# IO.net
KiCad netlist of a schematic drawn in Altium Designer
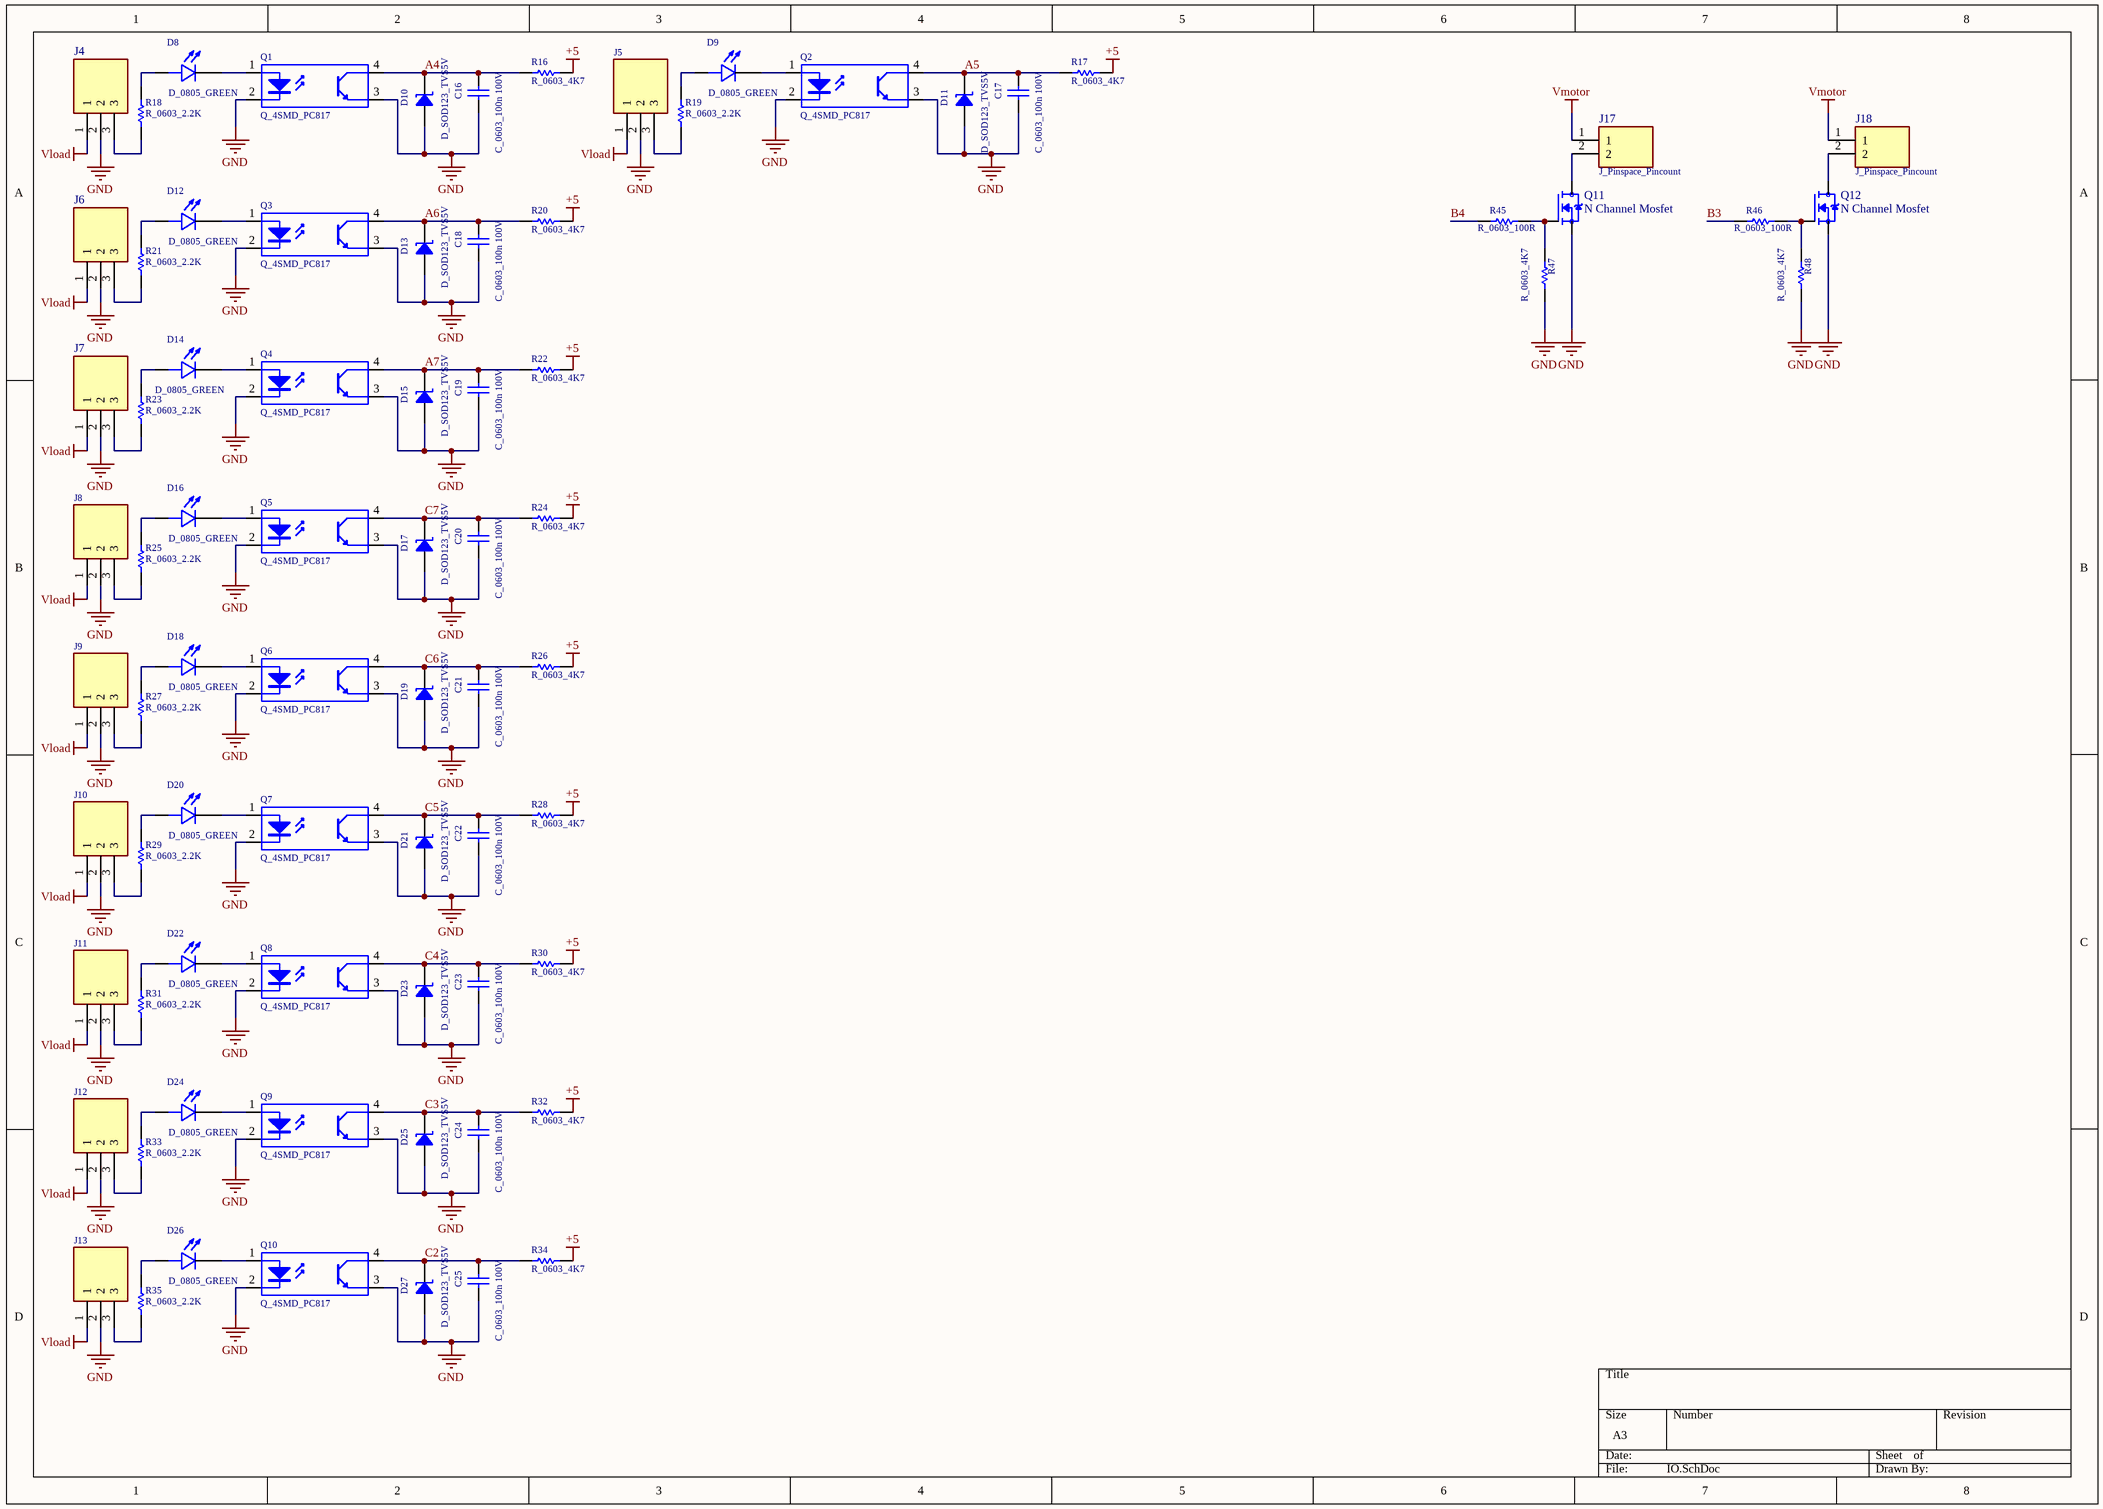
[diagram p0: IO.SchDoc]

(export (version "E")
  (design (tool "Eeschema 10.0.6"))
  (components
    (comp (ref "C16")
      (value "C_0603_100n 100V")
      (footprint "CAP 1206")
      (description "Capacitor")
      (fields (field (name "PUBLISHER") "Altium Limited"))
      (libsource (lib "HUE") (part "Cap"))
    )
    (comp (ref "C17")
      (value "C_0603_100n 100V")
      (footprint "CAP 1206")
      (description "Capacitor")
      (fields (field (name "PUBLISHER") "Altium Limited"))
      (libsource (lib "HUE") (part "Cap"))
    )
    (comp (ref "C18")
      (value "C_0603_100n 100V")
      (footprint "CAP 1206")
      (description "Capacitor")
      (fields (field (name "PUBLISHER") "Altium Limited"))
      (libsource (lib "HUE") (part "Cap"))
    )
    (comp (ref "C19")
      (value "C_0603_100n 100V")
      (footprint "CAP 1206")
      (description "Capacitor")
      (fields (field (name "PUBLISHER") "Altium Limited"))
      (libsource (lib "HUE") (part "Cap"))
    )
    (comp (ref "C20")
      (value "C_0603_100n 100V")
      (footprint "CAP 1206")
      (description "Capacitor")
      (fields (field (name "PUBLISHER") "Altium Limited"))
      (libsource (lib "HUE") (part "Cap"))
    )
    (comp (ref "C21")
      (value "C_0603_100n 100V")
      (footprint "CAP 1206")
      (description "Capacitor")
      (fields (field (name "PUBLISHER") "Altium Limited"))
      (libsource (lib "HUE") (part "Cap"))
    )
    (comp (ref "C22")
      (value "C_0603_100n 100V")
      (footprint "CAP 1206")
      (description "Capacitor")
      (fields (field (name "PUBLISHER") "Altium Limited"))
      (libsource (lib "HUE") (part "Cap"))
    )
    (comp (ref "C23")
      (value "C_0603_100n 100V")
      (footprint "CAP 1206")
      (description "Capacitor")
      (fields (field (name "PUBLISHER") "Altium Limited"))
      (libsource (lib "HUE") (part "Cap"))
    )
    (comp (ref "C24")
      (value "C_0603_100n 100V")
      (footprint "CAP 1206")
      (description "Capacitor")
      (fields (field (name "PUBLISHER") "Altium Limited"))
      (libsource (lib "HUE") (part "Cap"))
    )
    (comp (ref "C25")
      (value "C_0603_100n 100V")
      (footprint "CAP 1206")
      (description "Capacitor")
      (fields (field (name "PUBLISHER") "Altium Limited"))
      (libsource (lib "HUE") (part "Cap"))
    )
    (comp (ref "D8")
      (value "D_0805_GREEN")
      (footprint "Led 0603")
      (description "Led")
      (fields (field (name "MP") "SML-D12FWT86") (field (name "MF") "Rohm"))
      (libsource (lib "HUE") (part "Led"))
    )
    (comp (ref "D9")
      (value "D_0805_GREEN")
      (footprint "Led 0603")
      (description "Led")
      (fields (field (name "MP") "SML-D12FWT86") (field (name "MF") "Rohm"))
      (libsource (lib "HUE") (part "Led"))
    )
    (comp (ref "D10")
      (value "D_SOD123_TVS5V")
      (footprint "SOD-123")
      (description "Rectifier Diode")
      (libsource (lib "HUE") (part "DIODE TVS UNI"))
    )
    (comp (ref "D11")
      (value "D_SOD123_TVS5V")
      (footprint "SOD-123")
      (description "Rectifier Diode")
      (libsource (lib "HUE") (part "DIODE TVS UNI"))
    )
    (comp (ref "D12")
      (value "D_0805_GREEN")
      (footprint "Led 0603")
      (description "Led")
      (fields (field (name "MP") "SML-D12FWT86") (field (name "MF") "Rohm"))
      (libsource (lib "HUE") (part "Led"))
    )
    (comp (ref "D13")
      (value "D_SOD123_TVS5V")
      (footprint "SOD-123")
      (description "Rectifier Diode")
      (libsource (lib "HUE") (part "DIODE TVS UNI"))
    )
    (comp (ref "D14")
      (value "D_0805_GREEN")
      (footprint "Led 0603")
      (description "Led")
      (fields (field (name "MP") "SML-D12FWT86") (field (name "MF") "Rohm"))
      (libsource (lib "HUE") (part "Led"))
    )
    (comp (ref "D15")
      (value "D_SOD123_TVS5V")
      (footprint "SOD-123")
      (description "Rectifier Diode")
      (libsource (lib "HUE") (part "DIODE TVS UNI"))
    )
    (comp (ref "D16")
      (value "D_0805_GREEN")
      (footprint "Led 0603")
      (description "Led")
      (fields (field (name "MP") "SML-D12FWT86") (field (name "MF") "Rohm"))
      (libsource (lib "HUE") (part "Led"))
    )
    (comp (ref "D17")
      (value "D_SOD123_TVS5V")
      (footprint "SOD-123")
      (description "Rectifier Diode")
      (libsource (lib "HUE") (part "DIODE TVS UNI"))
    )
    (comp (ref "D18")
      (value "D_0805_GREEN")
      (footprint "Led 0603")
      (description "Led")
      (fields (field (name "MP") "SML-D12FWT86") (field (name "MF") "Rohm"))
      (libsource (lib "HUE") (part "Led"))
    )
    (comp (ref "D19")
      (value "D_SOD123_TVS5V")
      (footprint "SOD-123")
      (description "Rectifier Diode")
      (libsource (lib "HUE") (part "DIODE TVS UNI"))
    )
    (comp (ref "D20")
      (value "D_0805_GREEN")
      (footprint "Led 0603")
      (description "Led")
      (fields (field (name "MP") "SML-D12FWT86") (field (name "MF") "Rohm"))
      (libsource (lib "HUE") (part "Led"))
    )
    (comp (ref "D21")
      (value "D_SOD123_TVS5V")
      (footprint "SOD-123")
      (description "Rectifier Diode")
      (libsource (lib "HUE") (part "DIODE TVS UNI"))
    )
    (comp (ref "D22")
      (value "D_0805_GREEN")
      (footprint "Led 0603")
      (description "Led")
      (fields (field (name "MP") "SML-D12FWT86") (field (name "MF") "Rohm"))
      (libsource (lib "HUE") (part "Led"))
    )
    (comp (ref "D23")
      (value "D_SOD123_TVS5V")
      (footprint "SOD-123")
      (description "Rectifier Diode")
      (libsource (lib "HUE") (part "DIODE TVS UNI"))
    )
    (comp (ref "D24")
      (value "D_0805_GREEN")
      (footprint "Led 0603")
      (description "Led")
      (fields (field (name "MP") "SML-D12FWT86") (field (name "MF") "Rohm"))
      (libsource (lib "HUE") (part "Led"))
    )
    (comp (ref "D25")
      (value "D_SOD123_TVS5V")
      (footprint "SOD-123")
      (description "Rectifier Diode")
      (libsource (lib "HUE") (part "DIODE TVS UNI"))
    )
    (comp (ref "D26")
      (value "D_0805_GREEN")
      (footprint "Led 0603")
      (description "Led")
      (fields (field (name "MP") "SML-D12FWT86") (field (name "MF") "Rohm"))
      (libsource (lib "HUE") (part "Led"))
    )
    (comp (ref "D27")
      (value "D_SOD123_TVS5V")
      (footprint "SOD-123")
      (description "Rectifier Diode")
      (libsource (lib "HUE") (part "DIODE TVS UNI"))
    )
    (comp (ref "J4")
      (value "J_Pinspace_Pincount")
      (footprint "3 Pin PCB STB 5.08")
      (fields (field (name "MF") "{'manufacturer': u'CUI'}") (field (name "MP") "TBP02R1-381-03BE"))
      (libsource (lib "HUE") (part "3 Pin PCB Terminal Block"))
    )
    (comp (ref "J5")
      (value "J_Pinspace_Pincount")
      (footprint "3 Pin PCB STB 5.08")
      (fields (field (name "MF") "{'manufacturer': u'CUI'}") (field (name "MP") "TBP02R1-381-03BE"))
      (libsource (lib "HUE") (part "3 Pin PCB Terminal Block"))
    )
    (comp (ref "J6")
      (value "J_Pinspace_Pincount")
      (footprint "3 Pin PCB STB 5.08")
      (fields (field (name "MF") "{'manufacturer': u'CUI'}") (field (name "MP") "TBP02R1-381-03BE"))
      (libsource (lib "HUE") (part "3 Pin PCB Terminal Block"))
    )
    (comp (ref "J7")
      (value "J_Pinspace_Pincount")
      (footprint "3 Pin PCB STB 5.08")
      (fields (field (name "MF") "{'manufacturer': u'CUI'}") (field (name "MP") "TBP02R1-381-03BE"))
      (libsource (lib "HUE") (part "3 Pin PCB Terminal Block"))
    )
    (comp (ref "J8")
      (value "J_Pinspace_Pincount")
      (footprint "3 Pin PCB STB 5.08")
      (fields (field (name "MF") "{'manufacturer': u'CUI'}") (field (name "MP") "TBP02R1-381-03BE"))
      (libsource (lib "HUE") (part "3 Pin PCB Terminal Block"))
    )
    (comp (ref "J9")
      (value "J_Pinspace_Pincount")
      (footprint "3 Pin PCB STB 5.08")
      (fields (field (name "MF") "{'manufacturer': u'CUI'}") (field (name "MP") "TBP02R1-381-03BE"))
      (libsource (lib "HUE") (part "3 Pin PCB Terminal Block"))
    )
    (comp (ref "J10")
      (value "J_Pinspace_Pincount")
      (footprint "3 Pin PCB STB 5.08")
      (fields (field (name "MF") "{'manufacturer': u'CUI'}") (field (name "MP") "TBP02R1-381-03BE"))
      (libsource (lib "HUE") (part "3 Pin PCB Terminal Block"))
    )
    (comp (ref "J11")
      (value "J_Pinspace_Pincount")
      (footprint "3 Pin PCB STB 5.08")
      (fields (field (name "MF") "{'manufacturer': u'CUI'}") (field (name "MP") "TBP02R1-381-03BE"))
      (libsource (lib "HUE") (part "3 Pin PCB Terminal Block"))
    )
    (comp (ref "J12")
      (value "J_Pinspace_Pincount")
      (footprint "3 Pin PCB STB 5.08")
      (fields (field (name "MF") "{'manufacturer': u'CUI'}") (field (name "MP") "TBP02R1-381-03BE"))
      (libsource (lib "HUE") (part "3 Pin PCB Terminal Block"))
    )
    (comp (ref "J13")
      (value "J_Pinspace_Pincount")
      (footprint "3 Pin PCB STB 5.08")
      (fields (field (name "MF") "{'manufacturer': u'CUI'}") (field (name "MP") "TBP02R1-381-03BE"))
      (libsource (lib "HUE") (part "3 Pin PCB Terminal Block"))
    )
    (comp (ref "J17")
      (value "J_Pinspace_Pincount")
      (footprint "2 Pin PCB STB 5.08")
      (fields (field (name "MF") "CUI Devices") (field (name "MP") "TBP02R1-381-02BE"))
      (libsource (lib "HUE") (part "2 Pin PCB Terminal Block"))
    )
    (comp (ref "J18")
      (value "J_Pinspace_Pincount")
      (footprint "2 Pin PCB STB 5.08")
      (fields (field (name "MF") "CUI Devices") (field (name "MP") "TBP02R1-381-02BE"))
      (libsource (lib "HUE") (part "2 Pin PCB Terminal Block"))
    )
    (comp (ref "Q1")
      (value "Q_4SMD_PC817")
      (footprint "4-SMD")
      (description "Opto-Coupler")
      (libsource (lib "HUE") (part "Opto Coupler"))
    )
    (comp (ref "Q2")
      (value "Q_4SMD_PC817")
      (footprint "4-SMD")
      (description "Opto-Coupler")
      (libsource (lib "HUE") (part "Opto Coupler"))
    )
    (comp (ref "Q3")
      (value "Q_4SMD_PC817")
      (footprint "4-SMD")
      (description "Opto-Coupler")
      (libsource (lib "HUE") (part "Opto Coupler"))
    )
    (comp (ref "Q4")
      (value "Q_4SMD_PC817")
      (footprint "4-SMD")
      (description "Opto-Coupler")
      (libsource (lib "HUE") (part "Opto Coupler"))
    )
    (comp (ref "Q5")
      (value "Q_4SMD_PC817")
      (footprint "4-SMD")
      (description "Opto-Coupler")
      (libsource (lib "HUE") (part "Opto Coupler"))
    )
    (comp (ref "Q6")
      (value "Q_4SMD_PC817")
      (footprint "4-SMD")
      (description "Opto-Coupler")
      (libsource (lib "HUE") (part "Opto Coupler"))
    )
    (comp (ref "Q7")
      (value "Q_4SMD_PC817")
      (footprint "4-SMD")
      (description "Opto-Coupler")
      (libsource (lib "HUE") (part "Opto Coupler"))
    )
    (comp (ref "Q8")
      (value "Q_4SMD_PC817")
      (footprint "4-SMD")
      (description "Opto-Coupler")
      (libsource (lib "HUE") (part "Opto Coupler"))
    )
    (comp (ref "Q9")
      (value "Q_4SMD_PC817")
      (footprint "4-SMD")
      (description "Opto-Coupler")
      (libsource (lib "HUE") (part "Opto Coupler"))
    )
    (comp (ref "Q10")
      (value "Q_4SMD_PC817")
      (footprint "4-SMD")
      (description "Opto-Coupler")
      (libsource (lib "HUE") (part "Opto Coupler"))
    )
    (comp (ref "Q11")
      (value "N Channel Mosfet")
      (footprint "TO-252")
      (fields (field (name "MP") "IRLR2705PBF") (field (name "MF") "Infineon Technologies"))
      (libsource (lib "HUE") (part "N Channel Mosfet"))
    )
    (comp (ref "Q12")
      (value "N Channel Mosfet")
      (footprint "TO-252")
      (fields (field (name "MP") "IRLR2705PBF") (field (name "MF") "Infineon Technologies"))
      (libsource (lib "HUE") (part "N Channel Mosfet"))
    )
    (comp (ref "R16")
      (value "R_0603_4K7")
      (footprint "RES 1206")
      (description "Resistor")
      (fields (field (name "PUBLISHER") "Altium Limited"))
      (libsource (lib "HUE") (part "Res"))
    )
    (comp (ref "R17")
      (value "R_0603_4K7")
      (footprint "RES 1206")
      (description "Resistor")
      (fields (field (name "PUBLISHER") "Altium Limited"))
      (libsource (lib "HUE") (part "Res"))
    )
    (comp (ref "R18")
      (value "R_0603_2.2K")
      (footprint "RES 1206")
      (description "Resistor")
      (fields (field (name "PUBLISHER") "Altium Limited"))
      (libsource (lib "HUE") (part "Res"))
    )
    (comp (ref "R19")
      (value "R_0603_2.2K")
      (footprint "RES 1206")
      (description "Resistor")
      (fields (field (name "PUBLISHER") "Altium Limited"))
      (libsource (lib "HUE") (part "Res"))
    )
    (comp (ref "R20")
      (value "R_0603_4K7")
      (footprint "RES 1206")
      (description "Resistor")
      (fields (field (name "PUBLISHER") "Altium Limited"))
      (libsource (lib "HUE") (part "Res"))
    )
    (comp (ref "R21")
      (value "R_0603_2.2K")
      (footprint "RES 1206")
      (description "Resistor")
      (fields (field (name "PUBLISHER") "Altium Limited"))
      (libsource (lib "HUE") (part "Res"))
    )
    (comp (ref "R22")
      (value "R_0603_4K7")
      (footprint "RES 1206")
      (description "Resistor")
      (fields (field (name "PUBLISHER") "Altium Limited"))
      (libsource (lib "HUE") (part "Res"))
    )
    (comp (ref "R23")
      (value "R_0603_2.2K")
      (footprint "RES 1206")
      (description "Resistor")
      (fields (field (name "PUBLISHER") "Altium Limited"))
      (libsource (lib "HUE") (part "Res"))
    )
    (comp (ref "R24")
      (value "R_0603_4K7")
      (footprint "RES 1206")
      (description "Resistor")
      (fields (field (name "PUBLISHER") "Altium Limited"))
      (libsource (lib "HUE") (part "Res"))
    )
    (comp (ref "R25")
      (value "R_0603_2.2K")
      (footprint "RES 1206")
      (description "Resistor")
      (fields (field (name "PUBLISHER") "Altium Limited"))
      (libsource (lib "HUE") (part "Res"))
    )
    (comp (ref "R26")
      (value "R_0603_4K7")
      (footprint "RES 1206")
      (description "Resistor")
      (fields (field (name "PUBLISHER") "Altium Limited"))
      (libsource (lib "HUE") (part "Res"))
    )
    (comp (ref "R27")
      (value "R_0603_2.2K")
      (footprint "RES 1206")
      (description "Resistor")
      (fields (field (name "PUBLISHER") "Altium Limited"))
      (libsource (lib "HUE") (part "Res"))
    )
    (comp (ref "R28")
      (value "R_0603_4K7")
      (footprint "RES 1206")
      (description "Resistor")
      (fields (field (name "PUBLISHER") "Altium Limited"))
      (libsource (lib "HUE") (part "Res"))
    )
    (comp (ref "R29")
      (value "R_0603_2.2K")
      (footprint "RES 1206")
      (description "Resistor")
      (fields (field (name "PUBLISHER") "Altium Limited"))
      (libsource (lib "HUE") (part "Res"))
    )
    (comp (ref "R30")
      (value "R_0603_4K7")
      (footprint "RES 1206")
      (description "Resistor")
      (fields (field (name "PUBLISHER") "Altium Limited"))
      (libsource (lib "HUE") (part "Res"))
    )
    (comp (ref "R31")
      (value "R_0603_2.2K")
      (footprint "RES 1206")
      (description "Resistor")
      (fields (field (name "PUBLISHER") "Altium Limited"))
      (libsource (lib "HUE") (part "Res"))
    )
    (comp (ref "R32")
      (value "R_0603_4K7")
      (footprint "RES 1206")
      (description "Resistor")
      (fields (field (name "PUBLISHER") "Altium Limited"))
      (libsource (lib "HUE") (part "Res"))
    )
    (comp (ref "R33")
      (value "R_0603_2.2K")
      (footprint "RES 1206")
      (description "Resistor")
      (fields (field (name "PUBLISHER") "Altium Limited"))
      (libsource (lib "HUE") (part "Res"))
    )
    (comp (ref "R34")
      (value "R_0603_4K7")
      (footprint "RES 1206")
      (description "Resistor")
      (fields (field (name "PUBLISHER") "Altium Limited"))
      (libsource (lib "HUE") (part "Res"))
    )
    (comp (ref "R35")
      (value "R_0603_2.2K")
      (footprint "RES 1206")
      (description "Resistor")
      (fields (field (name "PUBLISHER") "Altium Limited"))
      (libsource (lib "HUE") (part "Res"))
    )
    (comp (ref "R45")
      (value "R_0603_100R")
      (footprint "RES 1206")
      (description "Resistor")
      (fields (field (name "PUBLISHER") "Altium Limited"))
      (libsource (lib "HUE") (part "Res"))
    )
    (comp (ref "R46")
      (value "R_0603_100R")
      (footprint "RES 1206")
      (description "Resistor")
      (fields (field (name "PUBLISHER") "Altium Limited"))
      (libsource (lib "HUE") (part "Res"))
    )
    (comp (ref "R47")
      (value "R_0603_4K7")
      (footprint "RES 1206")
      (description "Resistor")
      (fields (field (name "PUBLISHER") "Altium Limited"))
      (libsource (lib "HUE") (part "Res"))
    )
    (comp (ref "R48")
      (value "R_0603_4K7")
      (footprint "RES 1206")
      (description "Resistor")
      (fields (field (name "PUBLISHER") "Altium Limited"))
      (libsource (lib "HUE") (part "Res"))
    )
  )
  (nets
    (net (code "1") (name "+5") (class "Default")
      (node (ref "R16") (pin "1") (pinfunction "1_1") (pintype "passive"))
      (node (ref "R17") (pin "1") (pinfunction "1_1") (pintype "passive"))
      (node (ref "R20") (pin "1") (pinfunction "1_1") (pintype "passive"))
      (node (ref "R22") (pin "1") (pinfunction "1_1") (pintype "passive"))
      (node (ref "R24") (pin "1") (pinfunction "1_1") (pintype "passive"))
      (node (ref "R26") (pin "1") (pinfunction "1_1") (pintype "passive"))
      (node (ref "R28") (pin "1") (pinfunction "1_1") (pintype "passive"))
      (node (ref "R30") (pin "1") (pinfunction "1_1") (pintype "passive"))
      (node (ref "R32") (pin "1") (pinfunction "1_1") (pintype "passive"))
      (node (ref "R34") (pin "1") (pinfunction "1_1") (pintype "passive"))
    )
    (net (code "2") (name "/A4") (class "Default")
      (node (ref "C16") (pin "1") (pinfunction "1_1") (pintype "passive"))
      (node (ref "D10") (pin "2") (pinfunction "2_2") (pintype "passive"))
      (node (ref "Q1") (pin "4") (pinfunction "C_4") (pintype "passive"))
      (node (ref "R16") (pin "2") (pinfunction "2_2") (pintype "passive"))
    )
    (net (code "3") (name "/A5") (class "Default")
      (node (ref "C17") (pin "1") (pinfunction "1_1") (pintype "passive"))
      (node (ref "D11") (pin "2") (pinfunction "2_2") (pintype "passive"))
      (node (ref "Q2") (pin "4") (pinfunction "C_4") (pintype "passive"))
      (node (ref "R17") (pin "2") (pinfunction "2_2") (pintype "passive"))
    )
    (net (code "4") (name "/A6") (class "Default")
      (node (ref "C18") (pin "1") (pinfunction "1_1") (pintype "passive"))
      (node (ref "D13") (pin "2") (pinfunction "2_2") (pintype "passive"))
      (node (ref "Q3") (pin "4") (pinfunction "C_4") (pintype "passive"))
      (node (ref "R20") (pin "2") (pinfunction "2_2") (pintype "passive"))
    )
    (net (code "5") (name "/A7") (class "Default")
      (node (ref "C19") (pin "1") (pinfunction "1_1") (pintype "passive"))
      (node (ref "D15") (pin "2") (pinfunction "2_2") (pintype "passive"))
      (node (ref "Q4") (pin "4") (pinfunction "C_4") (pintype "passive"))
      (node (ref "R22") (pin "2") (pinfunction "2_2") (pintype "passive"))
    )
    (net (code "6") (name "/B3") (class "Default")
      (node (ref "R46") (pin "2") (pinfunction "2_2") (pintype "passive"))
    )
    (net (code "7") (name "/B4") (class "Default")
      (node (ref "R45") (pin "2") (pinfunction "2_2") (pintype "passive"))
    )
    (net (code "8") (name "/C2") (class "Default")
      (node (ref "C25") (pin "1") (pinfunction "1_1") (pintype "passive"))
      (node (ref "D27") (pin "2") (pinfunction "2_2") (pintype "passive"))
      (node (ref "Q10") (pin "4") (pinfunction "C_4") (pintype "passive"))
      (node (ref "R34") (pin "2") (pinfunction "2_2") (pintype "passive"))
    )
    (net (code "9") (name "/C3") (class "Default")
      (node (ref "C24") (pin "1") (pinfunction "1_1") (pintype "passive"))
      (node (ref "D25") (pin "2") (pinfunction "2_2") (pintype "passive"))
      (node (ref "Q9") (pin "4") (pinfunction "C_4") (pintype "passive"))
      (node (ref "R32") (pin "2") (pinfunction "2_2") (pintype "passive"))
    )
    (net (code "10") (name "/C4") (class "Default")
      (node (ref "C23") (pin "1") (pinfunction "1_1") (pintype "passive"))
      (node (ref "D23") (pin "2") (pinfunction "2_2") (pintype "passive"))
      (node (ref "Q8") (pin "4") (pinfunction "C_4") (pintype "passive"))
      (node (ref "R30") (pin "2") (pinfunction "2_2") (pintype "passive"))
    )
    (net (code "11") (name "/C5") (class "Default")
      (node (ref "C22") (pin "1") (pinfunction "1_1") (pintype "passive"))
      (node (ref "D21") (pin "2") (pinfunction "2_2") (pintype "passive"))
      (node (ref "Q7") (pin "4") (pinfunction "C_4") (pintype "passive"))
      (node (ref "R28") (pin "2") (pinfunction "2_2") (pintype "passive"))
    )
    (net (code "12") (name "/C6") (class "Default")
      (node (ref "C21") (pin "1") (pinfunction "1_1") (pintype "passive"))
      (node (ref "D19") (pin "2") (pinfunction "2_2") (pintype "passive"))
      (node (ref "Q6") (pin "4") (pinfunction "C_4") (pintype "passive"))
      (node (ref "R26") (pin "2") (pinfunction "2_2") (pintype "passive"))
    )
    (net (code "13") (name "/C7") (class "Default")
      (node (ref "C20") (pin "1") (pinfunction "1_1") (pintype "passive"))
      (node (ref "D17") (pin "2") (pinfunction "2_2") (pintype "passive"))
      (node (ref "Q5") (pin "4") (pinfunction "C_4") (pintype "passive"))
      (node (ref "R24") (pin "2") (pinfunction "2_2") (pintype "passive"))
    )
    (net (code "14") (name "GND") (class "Default")
      (node (ref "C16") (pin "2") (pinfunction "2_2") (pintype "passive"))
      (node (ref "C17") (pin "2") (pinfunction "2_2") (pintype "passive"))
      (node (ref "C18") (pin "2") (pinfunction "2_2") (pintype "passive"))
      (node (ref "C19") (pin "2") (pinfunction "2_2") (pintype "passive"))
      (node (ref "C20") (pin "2") (pinfunction "2_2") (pintype "passive"))
      (node (ref "C21") (pin "2") (pinfunction "2_2") (pintype "passive"))
      (node (ref "C22") (pin "2") (pinfunction "2_2") (pintype "passive"))
      (node (ref "C23") (pin "2") (pinfunction "2_2") (pintype "passive"))
      (node (ref "C24") (pin "2") (pinfunction "2_2") (pintype "passive"))
      (node (ref "C25") (pin "2") (pinfunction "2_2") (pintype "passive"))
      (node (ref "D10") (pin "1") (pinfunction "1_1") (pintype "passive"))
      (node (ref "D11") (pin "1") (pinfunction "1_1") (pintype "passive"))
      (node (ref "D13") (pin "1") (pinfunction "1_1") (pintype "passive"))
      (node (ref "D15") (pin "1") (pinfunction "1_1") (pintype "passive"))
      (node (ref "D17") (pin "1") (pinfunction "1_1") (pintype "passive"))
      (node (ref "D19") (pin "1") (pinfunction "1_1") (pintype "passive"))
      (node (ref "D21") (pin "1") (pinfunction "1_1") (pintype "passive"))
      (node (ref "D23") (pin "1") (pinfunction "1_1") (pintype "passive"))
      (node (ref "D25") (pin "1") (pinfunction "1_1") (pintype "passive"))
      (node (ref "D27") (pin "1") (pinfunction "1_1") (pintype "passive"))
      (node (ref "J10") (pin "2") (pinfunction "2_2") (pintype "passive"))
      (node (ref "J11") (pin "2") (pinfunction "2_2") (pintype "passive"))
      (node (ref "J12") (pin "2") (pinfunction "2_2") (pintype "passive"))
      (node (ref "J13") (pin "2") (pinfunction "2_2") (pintype "passive"))
      (node (ref "J4") (pin "2") (pinfunction "2_2") (pintype "passive"))
      (node (ref "J5") (pin "2") (pinfunction "2_2") (pintype "passive"))
      (node (ref "J6") (pin "2") (pinfunction "2_2") (pintype "passive"))
      (node (ref "J7") (pin "2") (pinfunction "2_2") (pintype "passive"))
      (node (ref "J8") (pin "2") (pinfunction "2_2") (pintype "passive"))
      (node (ref "J9") (pin "2") (pinfunction "2_2") (pintype "passive"))
      (node (ref "Q1") (pin "2") (pinfunction "K_2") (pintype "passive"))
      (node (ref "Q1") (pin "3") (pinfunction "E_3") (pintype "passive"))
      (node (ref "Q10") (pin "2") (pinfunction "K_2") (pintype "passive"))
      (node (ref "Q10") (pin "3") (pinfunction "E_3") (pintype "passive"))
      (node (ref "Q11") (pin "3") (pinfunction "S_3") (pintype "passive"))
      (node (ref "Q12") (pin "3") (pinfunction "S_3") (pintype "passive"))
      (node (ref "Q2") (pin "2") (pinfunction "K_2") (pintype "passive"))
      (node (ref "Q2") (pin "3") (pinfunction "E_3") (pintype "passive"))
      (node (ref "Q3") (pin "2") (pinfunction "K_2") (pintype "passive"))
      (node (ref "Q3") (pin "3") (pinfunction "E_3") (pintype "passive"))
      (node (ref "Q4") (pin "2") (pinfunction "K_2") (pintype "passive"))
      (node (ref "Q4") (pin "3") (pinfunction "E_3") (pintype "passive"))
      (node (ref "Q5") (pin "2") (pinfunction "K_2") (pintype "passive"))
      (node (ref "Q5") (pin "3") (pinfunction "E_3") (pintype "passive"))
      (node (ref "Q6") (pin "2") (pinfunction "K_2") (pintype "passive"))
      (node (ref "Q6") (pin "3") (pinfunction "E_3") (pintype "passive"))
      (node (ref "Q7") (pin "2") (pinfunction "K_2") (pintype "passive"))
      (node (ref "Q7") (pin "3") (pinfunction "E_3") (pintype "passive"))
      (node (ref "Q8") (pin "2") (pinfunction "K_2") (pintype "passive"))
      (node (ref "Q8") (pin "3") (pinfunction "E_3") (pintype "passive"))
      (node (ref "Q9") (pin "2") (pinfunction "K_2") (pintype "passive"))
      (node (ref "Q9") (pin "3") (pinfunction "E_3") (pintype "passive"))
      (node (ref "R47") (pin "2") (pinfunction "2_2") (pintype "passive"))
      (node (ref "R48") (pin "2") (pinfunction "2_2") (pintype "passive"))
    )
    (net (code "15") (name "Net-(D8-A)") (class "Default")
      (node (ref "D8") (pin "1") (pinfunction "A_1") (pintype "passive"))
      (node (ref "R18") (pin "2") (pinfunction "2_2") (pintype "passive"))
    )
    (net (code "16") (name "Net-(D8-C)") (class "Default")
      (node (ref "D8") (pin "2") (pinfunction "C_2") (pintype "passive"))
      (node (ref "Q1") (pin "1") (pinfunction "A_1") (pintype "passive"))
    )
    (net (code "17") (name "Net-(D9-A)") (class "Default")
      (node (ref "D9") (pin "1") (pinfunction "A_1") (pintype "passive"))
      (node (ref "R19") (pin "2") (pinfunction "2_2") (pintype "passive"))
    )
    (net (code "18") (name "Net-(D9-C)") (class "Default")
      (node (ref "D9") (pin "2") (pinfunction "C_2") (pintype "passive"))
      (node (ref "Q2") (pin "1") (pinfunction "A_1") (pintype "passive"))
    )
    (net (code "19") (name "Net-(D12-A)") (class "Default")
      (node (ref "D12") (pin "1") (pinfunction "A_1") (pintype "passive"))
      (node (ref "R21") (pin "2") (pinfunction "2_2") (pintype "passive"))
    )
    (net (code "20") (name "Net-(D12-C)") (class "Default")
      (node (ref "D12") (pin "2") (pinfunction "C_2") (pintype "passive"))
      (node (ref "Q3") (pin "1") (pinfunction "A_1") (pintype "passive"))
    )
    (net (code "21") (name "Net-(D14-A)") (class "Default")
      (node (ref "D14") (pin "1") (pinfunction "A_1") (pintype "passive"))
      (node (ref "R23") (pin "2") (pinfunction "2_2") (pintype "passive"))
    )
    (net (code "22") (name "Net-(D14-C)") (class "Default")
      (node (ref "D14") (pin "2") (pinfunction "C_2") (pintype "passive"))
      (node (ref "Q4") (pin "1") (pinfunction "A_1") (pintype "passive"))
    )
    (net (code "23") (name "Net-(D16-A)") (class "Default")
      (node (ref "D16") (pin "1") (pinfunction "A_1") (pintype "passive"))
      (node (ref "R25") (pin "2") (pinfunction "2_2") (pintype "passive"))
    )
    (net (code "24") (name "Net-(D16-C)") (class "Default")
      (node (ref "D16") (pin "2") (pinfunction "C_2") (pintype "passive"))
      (node (ref "Q5") (pin "1") (pinfunction "A_1") (pintype "passive"))
    )
    (net (code "25") (name "Net-(D18-A)") (class "Default")
      (node (ref "D18") (pin "1") (pinfunction "A_1") (pintype "passive"))
      (node (ref "R27") (pin "2") (pinfunction "2_2") (pintype "passive"))
    )
    (net (code "26") (name "Net-(D18-C)") (class "Default")
      (node (ref "D18") (pin "2") (pinfunction "C_2") (pintype "passive"))
      (node (ref "Q6") (pin "1") (pinfunction "A_1") (pintype "passive"))
    )
    (net (code "27") (name "Net-(D20-A)") (class "Default")
      (node (ref "D20") (pin "1") (pinfunction "A_1") (pintype "passive"))
      (node (ref "R29") (pin "2") (pinfunction "2_2") (pintype "passive"))
    )
    (net (code "28") (name "Net-(D20-C)") (class "Default")
      (node (ref "D20") (pin "2") (pinfunction "C_2") (pintype "passive"))
      (node (ref "Q7") (pin "1") (pinfunction "A_1") (pintype "passive"))
    )
    (net (code "29") (name "Net-(D22-A)") (class "Default")
      (node (ref "D22") (pin "1") (pinfunction "A_1") (pintype "passive"))
      (node (ref "R31") (pin "2") (pinfunction "2_2") (pintype "passive"))
    )
    (net (code "30") (name "Net-(D22-C)") (class "Default")
      (node (ref "D22") (pin "2") (pinfunction "C_2") (pintype "passive"))
      (node (ref "Q8") (pin "1") (pinfunction "A_1") (pintype "passive"))
    )
    (net (code "31") (name "Net-(D24-A)") (class "Default")
      (node (ref "D24") (pin "1") (pinfunction "A_1") (pintype "passive"))
      (node (ref "R33") (pin "2") (pinfunction "2_2") (pintype "passive"))
    )
    (net (code "32") (name "Net-(D24-C)") (class "Default")
      (node (ref "D24") (pin "2") (pinfunction "C_2") (pintype "passive"))
      (node (ref "Q9") (pin "1") (pinfunction "A_1") (pintype "passive"))
    )
    (net (code "33") (name "Net-(D26-A)") (class "Default")
      (node (ref "D26") (pin "1") (pinfunction "A_1") (pintype "passive"))
      (node (ref "R35") (pin "2") (pinfunction "2_2") (pintype "passive"))
    )
    (net (code "34") (name "Net-(D26-C)") (class "Default")
      (node (ref "D26") (pin "2") (pinfunction "C_2") (pintype "passive"))
      (node (ref "Q10") (pin "1") (pinfunction "A_1") (pintype "passive"))
    )
    (net (code "35") (name "Net-(J4-Pad3)") (class "Default")
      (node (ref "J4") (pin "3") (pinfunction "3_3") (pintype "passive"))
      (node (ref "R18") (pin "1") (pinfunction "1_1") (pintype "passive"))
    )
    (net (code "36") (name "Net-(J5-Pad3)") (class "Default")
      (node (ref "J5") (pin "3") (pinfunction "3_3") (pintype "passive"))
      (node (ref "R19") (pin "1") (pinfunction "1_1") (pintype "passive"))
    )
    (net (code "37") (name "Net-(J6-Pad3)") (class "Default")
      (node (ref "J6") (pin "3") (pinfunction "3_3") (pintype "passive"))
      (node (ref "R21") (pin "1") (pinfunction "1_1") (pintype "passive"))
    )
    (net (code "38") (name "Net-(J7-Pad3)") (class "Default")
      (node (ref "J7") (pin "3") (pinfunction "3_3") (pintype "passive"))
      (node (ref "R23") (pin "1") (pinfunction "1_1") (pintype "passive"))
    )
    (net (code "39") (name "Net-(J8-Pad3)") (class "Default")
      (node (ref "J8") (pin "3") (pinfunction "3_3") (pintype "passive"))
      (node (ref "R25") (pin "1") (pinfunction "1_1") (pintype "passive"))
    )
    (net (code "40") (name "Net-(J9-Pad3)") (class "Default")
      (node (ref "J9") (pin "3") (pinfunction "3_3") (pintype "passive"))
      (node (ref "R27") (pin "1") (pinfunction "1_1") (pintype "passive"))
    )
    (net (code "41") (name "Net-(J10-Pad3)") (class "Default")
      (node (ref "J10") (pin "3") (pinfunction "3_3") (pintype "passive"))
      (node (ref "R29") (pin "1") (pinfunction "1_1") (pintype "passive"))
    )
    (net (code "42") (name "Net-(J11-Pad3)") (class "Default")
      (node (ref "J11") (pin "3") (pinfunction "3_3") (pintype "passive"))
      (node (ref "R31") (pin "1") (pinfunction "1_1") (pintype "passive"))
    )
    (net (code "43") (name "Net-(J12-Pad3)") (class "Default")
      (node (ref "J12") (pin "3") (pinfunction "3_3") (pintype "passive"))
      (node (ref "R33") (pin "1") (pinfunction "1_1") (pintype "passive"))
    )
    (net (code "44") (name "Net-(J13-Pad3)") (class "Default")
      (node (ref "J13") (pin "3") (pinfunction "3_3") (pintype "passive"))
      (node (ref "R35") (pin "1") (pinfunction "1_1") (pintype "passive"))
    )
    (net (code "45") (name "Net-(Q11-D)") (class "Default")
      (node (ref "J17") (pin "2") (pinfunction "2_2") (pintype "passive"))
      (node (ref "Q11") (pin "4") (pinfunction "D_4") (pintype "passive"))
    )
    (net (code "46") (name "Net-(Q11-G)") (class "Default")
      (node (ref "Q11") (pin "1") (pinfunction "G_1") (pintype "passive"))
      (node (ref "R45") (pin "1") (pinfunction "1_1") (pintype "passive"))
      (node (ref "R47") (pin "1") (pinfunction "1_1") (pintype "passive"))
    )
    (net (code "47") (name "Net-(Q12-D)") (class "Default")
      (node (ref "J18") (pin "2") (pinfunction "2_2") (pintype "passive"))
      (node (ref "Q12") (pin "4") (pinfunction "D_4") (pintype "passive"))
    )
    (net (code "48") (name "Net-(Q12-G)") (class "Default")
      (node (ref "Q12") (pin "1") (pinfunction "G_1") (pintype "passive"))
      (node (ref "R46") (pin "1") (pinfunction "1_1") (pintype "passive"))
      (node (ref "R48") (pin "1") (pinfunction "1_1") (pintype "passive"))
    )
    (net (code "49") (name "Vload") (class "Default")
      (node (ref "J10") (pin "1") (pinfunction "1_1") (pintype "passive"))
      (node (ref "J11") (pin "1") (pinfunction "1_1") (pintype "passive"))
      (node (ref "J12") (pin "1") (pinfunction "1_1") (pintype "passive"))
      (node (ref "J13") (pin "1") (pinfunction "1_1") (pintype "passive"))
      (node (ref "J4") (pin "1") (pinfunction "1_1") (pintype "passive"))
      (node (ref "J5") (pin "1") (pinfunction "1_1") (pintype "passive"))
      (node (ref "J6") (pin "1") (pinfunction "1_1") (pintype "passive"))
      (node (ref "J7") (pin "1") (pinfunction "1_1") (pintype "passive"))
      (node (ref "J8") (pin "1") (pinfunction "1_1") (pintype "passive"))
      (node (ref "J9") (pin "1") (pinfunction "1_1") (pintype "passive"))
    )
    (net (code "50") (name "Vmotor") (class "Default")
      (node (ref "J17") (pin "1") (pinfunction "1_1") (pintype "passive"))
      (node (ref "J18") (pin "1") (pinfunction "1_1") (pintype "passive"))
    )
  )
)
